# I2C_IO_Expander.net
KiCad netlist of a schematic drawn in Altium Designer
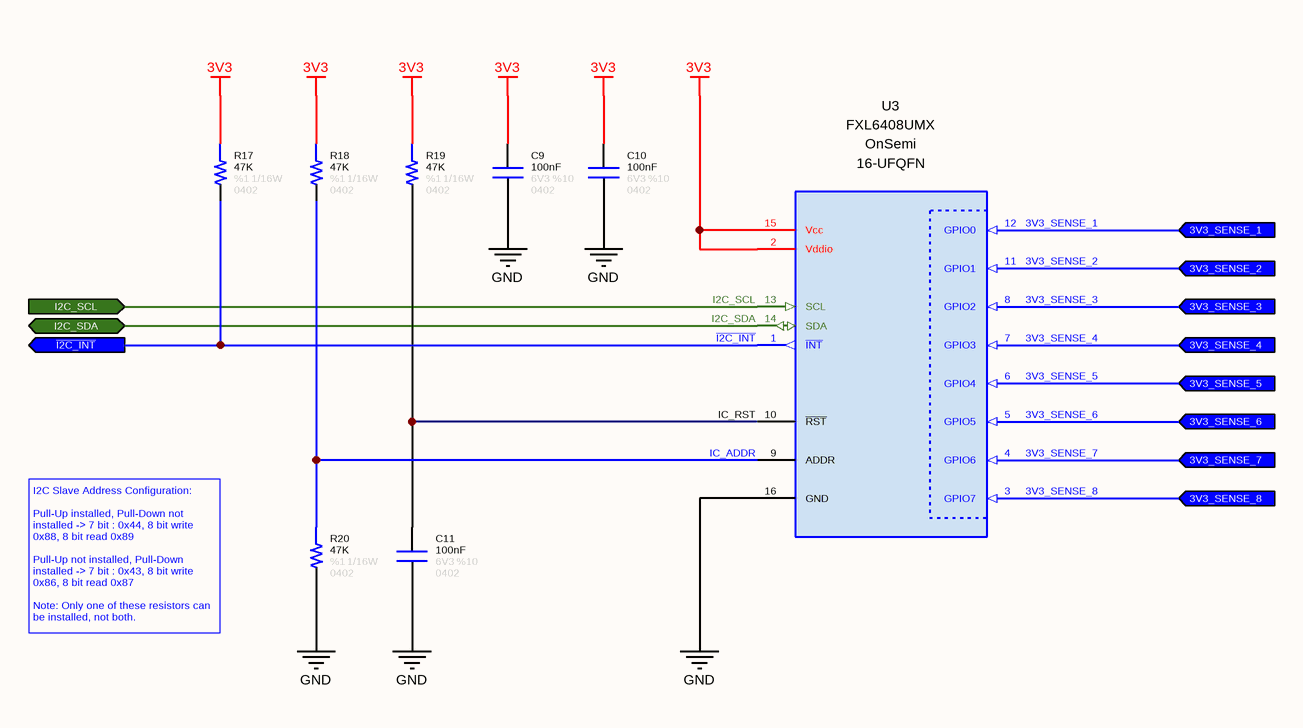
[diagram p0: I2C IO Expander.SchDoc]

(export (version "E")
  (design (tool "Eeschema 10.0.6"))
  (components
    (comp (ref "C9")
      (value "100nF")
      (footprint "CAPACITOR_0402")
      (description "Capacitor - 100nF [0402-6V3] (Ceramic)")
      (fields
        (field (name "MANUFACTURER PART NUMBER") "04026D104KAT4A")
        (field (name "TOLERANCE") "%10")
        (field (name "VOLTAGE") "6V3")
        (field (name "CASE") "0402")
        (field (name "Comment") "Capacitor - 100nF [0402] (Ceramic)")
      )
      (libsource (lib "Akkoyun") (part "Capacitor - 100nF [0402-6V3]"))
    )
    (comp (ref "C10")
      (value "100nF")
      (footprint "CAPACITOR_0402")
      (description "Capacitor - 100nF [0402-6V3] (Ceramic)")
      (fields
        (field (name "MANUFACTURER PART NUMBER") "04026D104KAT4A")
        (field (name "TOLERANCE") "%10")
        (field (name "VOLTAGE") "6V3")
        (field (name "CASE") "0402")
        (field (name "Comment") "Capacitor - 100nF [0402] (Ceramic)")
      )
      (libsource (lib "Akkoyun") (part "Capacitor - 100nF [0402-6V3]"))
    )
    (comp (ref "C11")
      (value "100nF")
      (footprint "CAPACITOR_0402")
      (description "Capacitor - 100nF [0402-6V3] (Ceramic)")
      (fields
        (field (name "MANUFACTURER PART NUMBER") "04026D104KAT4A")
        (field (name "TOLERANCE") "%10")
        (field (name "VOLTAGE") "6V3")
        (field (name "CASE") "0402")
        (field (name "Comment") "Capacitor - 100nF [0402] (Ceramic)")
      )
      (libsource (lib "Akkoyun") (part "Capacitor - 100nF [0402-6V3]"))
    )
    (comp (ref "R17")
      (value "47K")
      (footprint "RESISTOR_0402")
      (description "Thick Film Resistors - SMD 1/16 W 47 KOhm 1%")
      (fields
        (field (name "MANUFACTURER PART NUMBER") "CRCW040247K0FKED")
        (field (name "TOLERANCE") "%1")
        (field (name "CASE") "0402")
        (field (name "POWER") "1/16W")
        (field (name "Comment") "47K - 0402 - %1 - 1/16W")
      )
      (libsource (lib "Akkoyun") (part "Resistor - 47K [0402]"))
    )
    (comp (ref "R18")
      (value "47K")
      (footprint "RESISTOR_0402")
      (description "Thick Film Resistors - SMD 1/16 W 47 KOhm 1%")
      (fields
        (field (name "MANUFACTURER PART NUMBER") "CRCW040247K0FKED")
        (field (name "TOLERANCE") "%1")
        (field (name "CASE") "0402")
        (field (name "POWER") "1/16W")
        (field (name "Comment") "47K - 0402 - %1 - 1/16W")
      )
      (libsource (lib "Akkoyun") (part "Resistor - 47K [0402]"))
    )
    (comp (ref "R19")
      (value "47K")
      (footprint "RESISTOR_0402")
      (description "Thick Film Resistors - SMD 1/16 W 47 KOhm 1%")
      (fields
        (field (name "MANUFACTURER PART NUMBER") "CRCW040247K0FKED")
        (field (name "TOLERANCE") "%1")
        (field (name "CASE") "0402")
        (field (name "POWER") "1/16W")
        (field (name "Comment") "47K - 0402 - %1 - 1/16W")
      )
      (libsource (lib "Akkoyun") (part "Resistor - 47K [0402]"))
    )
    (comp (ref "R20")
      (value "47K")
      (footprint "RESISTOR_0402")
      (description "Thick Film Resistors - SMD 1/16 W 47 KOhm 1%")
      (fields
        (field (name "MANUFACTURER PART NUMBER") "CRCW040247K0FKED")
        (field (name "TOLERANCE") "%1")
        (field (name "CASE") "0402")
        (field (name "POWER") "1/16W")
        (field (name "Comment") "47K - 0402 - %1 - 1/16W")
      )
      (libsource (lib "Akkoyun") (part "Resistor - 47K [0402]"))
    )
    (comp (ref "U3")
      (value "FXL6408UMX")
      (footprint "16-UFQFN")
      (description "IC GPIO EXPANDER I2C 8B 16-UMLP")
      (fields
        (field (name "MANUFACTURER NAME") "FXL6408UMX")
        (field (name "MANUFACTURER PART NUMBER") "OnSemi")
        (field (name "CASE") "16-UFQFN")
      )
      (libsource (lib "Akkoyun") (part "IC - FXL6408UMX"))
    )
  )
  (nets
    (net (code "1") (name "/3V3_SENSE_1") (class "Default")
      (node (ref "U3") (pin "12") (pinfunction "GPIO0_12") (pintype "input"))
    )
    (net (code "2") (name "/3V3_SENSE_2") (class "Default")
      (node (ref "U3") (pin "11") (pinfunction "GPIO1_11") (pintype "input"))
    )
    (net (code "3") (name "/3V3_SENSE_3") (class "Default")
      (node (ref "U3") (pin "8") (pinfunction "GPIO2_8") (pintype "input"))
    )
    (net (code "4") (name "/3V3_SENSE_4") (class "Default")
      (node (ref "U3") (pin "7") (pinfunction "GPIO3_7") (pintype "input"))
    )
    (net (code "5") (name "/3V3_SENSE_5") (class "Default")
      (node (ref "U3") (pin "6") (pinfunction "GPIO4_6") (pintype "input"))
    )
    (net (code "6") (name "/3V3_SENSE_6") (class "Default")
      (node (ref "U3") (pin "5") (pinfunction "GPIO5_5") (pintype "input"))
    )
    (net (code "7") (name "/3V3_SENSE_7") (class "Default")
      (node (ref "U3") (pin "4") (pinfunction "GPIO6_4") (pintype "input"))
    )
    (net (code "8") (name "/3V3_SENSE_8") (class "Default")
      (node (ref "U3") (pin "3") (pinfunction "GPIO7_3") (pintype "input"))
    )
    (net (code "9") (name "/I2C_SCL") (class "Default")
      (node (ref "U3") (pin "13") (pinfunction "SCL_13") (pintype "input"))
    )
    (net (code "10") (name "/I2C_SDA") (class "Default")
      (node (ref "U3") (pin "14") (pinfunction "SDA_14") (pintype "bidirectional"))
    )
    (net (code "11") (name "/IC_ADDR") (class "Default")
      (node (ref "R18") (pin "1") (pinfunction "1_1") (pintype "passive"))
      (node (ref "R20") (pin "2") (pinfunction "2_2") (pintype "passive"))
      (node (ref "U3") (pin "9") (pinfunction "ADDR_9") (pintype "passive"))
    )
    (net (code "12") (name "/IC_RST") (class "Default")
      (node (ref "C11") (pin "2") (pinfunction "2_2") (pintype "passive"))
      (node (ref "R19") (pin "1") (pinfunction "1_1") (pintype "passive"))
      (node (ref "U3") (pin "10") (pinfunction "~{RST}_10") (pintype "passive"))
    )
    (net (code "13") (name "/~{I2C_INT}") (class "Default")
      (node (ref "R17") (pin "1") (pinfunction "1_1") (pintype "passive"))
      (node (ref "U3") (pin "1") (pinfunction "~{INT}_1") (pintype "output"))
    )
    (net (code "14") (name "3V3") (class "Default")
      (node (ref "C10") (pin "2") (pinfunction "2_2") (pintype "passive"))
      (node (ref "C9") (pin "2") (pinfunction "2_2") (pintype "passive"))
      (node (ref "R17") (pin "2") (pinfunction "2_2") (pintype "passive"))
      (node (ref "R18") (pin "2") (pinfunction "2_2") (pintype "passive"))
      (node (ref "R19") (pin "2") (pinfunction "2_2") (pintype "passive"))
      (node (ref "U3") (pin "15") (pinfunction "Vcc_15") (pintype "power_in"))
      (node (ref "U3") (pin "2") (pinfunction "Vddio_2") (pintype "power_in"))
    )
    (net (code "15") (name "GND") (class "Default")
      (node (ref "C10") (pin "1") (pinfunction "1_1") (pintype "passive"))
      (node (ref "C11") (pin "1") (pinfunction "1_1") (pintype "passive"))
      (node (ref "C9") (pin "1") (pinfunction "1_1") (pintype "passive"))
      (node (ref "R20") (pin "1") (pinfunction "1_1") (pintype "passive"))
      (node (ref "U3") (pin "16") (pinfunction "GND_16") (pintype "power_in"))
    )
  )
)
